# Allimentations.net
KiCad netlist of a schematic drawn in Altium Designer
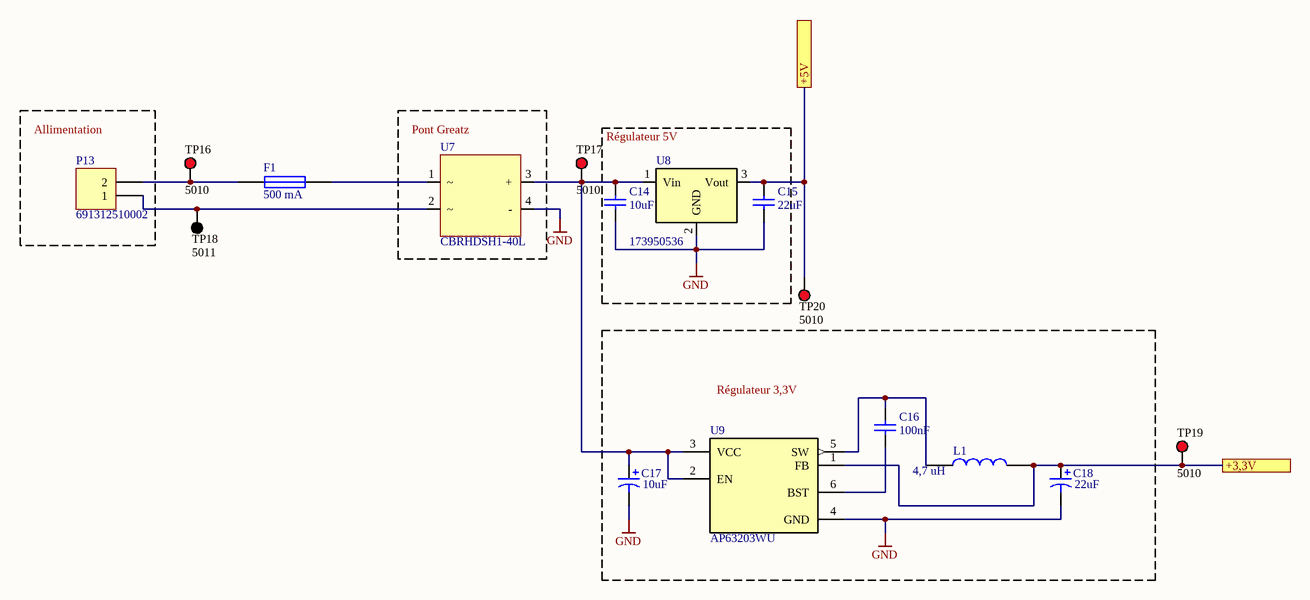
[diagram p0: Allimentations.SchDoc]

(export (version "E")
  (design (tool "Eeschema 10.0.6"))
  (components
    (comp (ref "C14")
      (value "10uF")
      (footprint "C0805")
      (description "Capacitor")
      (fields (field (name "Comment") "Cap") (field (name "PUBLISHER") "Altium Limited"))
      (libsource (lib "Miscellaneous Devices") (part "Cap"))
    )
    (comp (ref "C15")
      (value "22uF")
      (footprint "C0805")
      (description "Capacitor")
      (fields (field (name "Comment") "Cap") (field (name "PUBLISHER") "Altium Limited"))
      (libsource (lib "Miscellaneous Devices") (part "Cap"))
    )
    (comp (ref "C16")
      (value "100nF")
      (footprint "C0805")
      (description "Capacitor")
      (fields (field (name "Comment") "Cap") (field (name "PUBLISHER") "Altium Limited"))
      (libsource (lib "Miscellaneous Devices") (part "Cap"))
    )
    (comp (ref "C17")
      (value "10uF")
      (footprint "CAP_EEEFK1E331GP")
      (description "Polarized Capacitor (Radial)")
      (fields (field (name "Comment") "Cap Pol1") (field (name "PUBLISHER") "Altium Limited"))
      (libsource (lib "Miscellaneous Devices") (part "Cap Pol1"))
    )
    (comp (ref "C18")
      (value "22uF")
      (footprint "CAP_EEEFK1E331GP")
      (description "Polarized Capacitor (Radial)")
      (fields (field (name "Comment") "Cap Pol1") (field (name "PUBLISHER") "Altium Limited"))
      (libsource (lib "Miscellaneous Devices") (part "Cap Pol1"))
    )
    (comp (ref "F1")
      (value "500 mA")
      (footprint "PIN-W2/E2.8")
      (description "Fuse")
      (fields (field (name "PUBLISHER") "Altium Limited"))
      (libsource (lib "Miscellaneous Devices") (part "Fuse 1"))
    )
    (comp (ref "L1")
      (value "4,7 uH")
      (footprint "CDRH125101MC")
      (description "Fixed Inductors 22uH 2.80A 0.028ohms")
      (fields (field (name "MANUFACTURER_PART_NUMBER") "CDRH125NP-220MC"))
      (libsource (lib "TP2_Convertisseur_Courant") (part "CDRH125NP-220MC"))
    )
    (comp (ref "P13")
      (value "691312510002")
      (footprint "691312710002")
      (description "Header, 2-Pin")
      (fields (field (name "PUBLISHER") "Altium Limited"))
      (libsource (lib "Miscellaneous Connectors") (part "MHDR1X2"))
    )
    (comp (ref "TP16")
      (value "5010")
      (footprint "KSTN-5010_V")
      (description "Test Point, Red, Through Hole, RoHS, Bulk")
      (fields (field (name "MANUFACTURER") "Keystone"))
      (libsource (lib "Altium Content Vault") (part "TESTPOINT_RED"))
    )
    (comp (ref "TP17")
      (value "5010")
      (footprint "KSTN-5010_V")
      (description "Test Point, Red, Through Hole, RoHS, Bulk")
      (fields (field (name "MANUFACTURER") "Keystone"))
      (libsource (lib "Altium Content Vault") (part "TESTPOINT_RED"))
    )
    (comp (ref "TP18")
      (value "5011")
      (footprint "KSTN-5011_V")
      (description "Test Point, Black, Through Hole, RoHS, Bulk")
      (fields (field (name "MANUFACTURER") "Keystone"))
      (libsource (lib "Altium Content Vault") (part "TESTPOINT_BLACK"))
    )
    (comp (ref "TP19")
      (value "5010")
      (footprint "KSTN-5010_V")
      (description "Test Point, Red, Through Hole, RoHS, Bulk")
      (fields (field (name "MANUFACTURER") "Keystone"))
      (libsource (lib "Altium Content Vault") (part "TESTPOINT_RED"))
    )
    (comp (ref "TP20")
      (value "5010")
      (footprint "KSTN-5010_V")
      (description "Test Point, Red, Through Hole, RoHS, Bulk")
      (fields (field (name "MANUFACTURER") "Keystone"))
      (libsource (lib "Altium Content Vault") (part "TESTPOINT_RED"))
    )
    (comp (ref "U7")
      (value "CBRHDSH1-40L")
      (footprint "CBRHDSH1-40L")
      (libsource (lib "2227_BoiteBruitage") (part "CBRHDSH1-40L"))
    )
    (comp (ref "U8")
      (value "173950536")
      (footprint "173950536")
      (libsource (lib "2227_BoiteBruitage") (part "173950536"))
    )
    (comp (ref "U9")
      (value "AP63203WU")
      (footprint "AP63203WU")
      (libsource (lib "2227_BoiteBruitage") (part "AP63203WU"))
    )
  )
  (nets
    (net (code "1") (name "/+3,3V") (class "Default")
      (node (ref "C18") (pin "1") (pinfunction "1_1") (pintype "passive"))
      (node (ref "L1") (pin "2") (pinfunction "2_2") (pintype "passive"))
      (node (ref "TP19") (pin "1") (pinfunction "1_1") (pintype "passive"))
      (node (ref "U9") (pin "1") (pinfunction "FB_1") (pintype "passive"))
    )
    (net (code "2") (name "/+5V") (class "Default")
      (node (ref "C15") (pin "2") (pinfunction "2_2") (pintype "passive"))
      (node (ref "TP20") (pin "1") (pinfunction "1_1") (pintype "passive"))
      (node (ref "U8") (pin "3") (pinfunction "Vout_3") (pintype "passive"))
    )
    (net (code "3") (name "GND") (class "Default")
      (node (ref "C14") (pin "1") (pinfunction "1_1") (pintype "passive"))
      (node (ref "C15") (pin "1") (pinfunction "1_1") (pintype "passive"))
      (node (ref "C17") (pin "2") (pinfunction "2_2") (pintype "passive"))
      (node (ref "C18") (pin "2") (pinfunction "2_2") (pintype "passive"))
      (node (ref "U7") (pin "4") (pinfunction "-_4") (pintype "passive"))
      (node (ref "U8") (pin "2") (pinfunction "GND_2") (pintype "passive"))
      (node (ref "U9") (pin "4") (pinfunction "GND_4") (pintype "power_in"))
    )
    (net (code "4") (name "Net-(F1-Pad1)") (class "Default")
      (node (ref "F1") (pin "1") (pinfunction "1_1") (pintype "passive"))
      (node (ref "P13") (pin "2") (pinfunction "2_2") (pintype "passive"))
      (node (ref "TP16") (pin "1") (pinfunction "1_1") (pintype "passive"))
    )
    (net (code "5") (name "Net-(F1-Pad2)") (class "Default")
      (node (ref "F1") (pin "2") (pinfunction "2_2") (pintype "passive"))
      (node (ref "U7") (pin "1") (pinfunction "~_1") (pintype "passive"))
    )
    (net (code "6") (name "Net-(P13-Pad1)") (class "Default")
      (node (ref "P13") (pin "1") (pinfunction "1_1") (pintype "passive"))
      (node (ref "TP18") (pin "1") (pinfunction "1_1") (pintype "passive"))
      (node (ref "U7") (pin "2") (pinfunction "~_2") (pintype "passive"))
    )
    (net (code "7") (name "Net-(U7-+)") (class "Default")
      (node (ref "C14") (pin "2") (pinfunction "2_2") (pintype "passive"))
      (node (ref "C17") (pin "1") (pinfunction "1_1") (pintype "passive"))
      (node (ref "TP17") (pin "1") (pinfunction "1_1") (pintype "passive"))
      (node (ref "U7") (pin "3") (pinfunction "+_3") (pintype "passive"))
      (node (ref "U8") (pin "1") (pinfunction "Vin_1") (pintype "passive"))
      (node (ref "U9") (pin "2") (pinfunction "EN_2") (pintype "passive"))
      (node (ref "U9") (pin "3") (pinfunction "VCC_3") (pintype "passive"))
    )
    (net (code "8") (name "Net-(U9-BST)") (class "Default")
      (node (ref "C16") (pin "1") (pinfunction "1_1") (pintype "passive"))
      (node (ref "U9") (pin "6") (pinfunction "BST_6") (pintype "power_in"))
    )
    (net (code "9") (name "Net-(U9-SW)") (class "Default")
      (node (ref "C16") (pin "2") (pinfunction "2_2") (pintype "passive"))
      (node (ref "L1") (pin "1") (pinfunction "1_1") (pintype "passive"))
      (node (ref "U9") (pin "5") (pinfunction "SW_5") (pintype "output"))
    )
  )
)
